# Isolation.net
KiCad netlist of a schematic drawn in Altium Designer
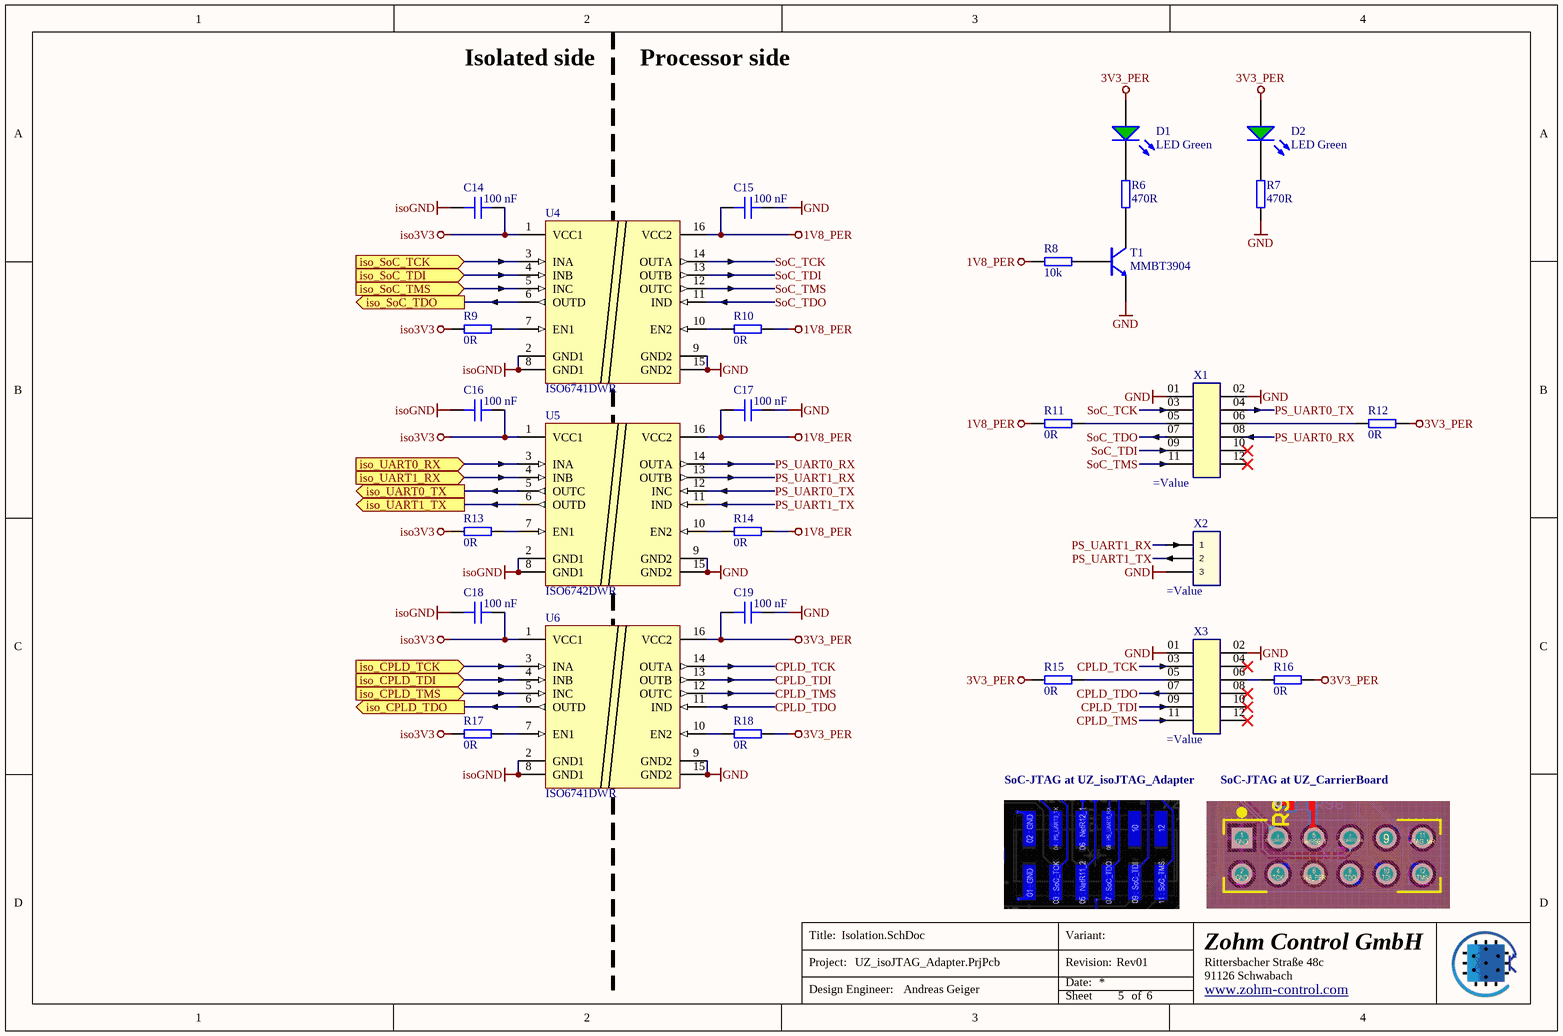
[diagram p0: Isolation.SchDoc]

(export (version "E")
  (design (tool "Eeschema 10.0.6"))
  (components
    (comp (ref "C14")
      (value "100 nF")
      (footprint "C_0402_TE")
      (description "50V 100nF X7R ±10% 0402 Multilayer Ceramic Capacitors MLCC - SMD/SMT ROHS")
      (fields
        (field (name "MANUFACTURER PART NUMBER") "GRM155R71H104KE14D")
        (field (name "MANUFACTURER") "Murata Electronics")
        (field (name "CREATED FROM") "AGeiger")
      )
      (libsource (lib "user") (part "Capacitor"))
    )
    (comp (ref "C15")
      (value "100 nF")
      (footprint "C_0402_TE")
      (description "50V 100nF X7R ±10% 0402 Multilayer Ceramic Capacitors MLCC - SMD/SMT ROHS")
      (fields
        (field (name "MANUFACTURER PART NUMBER") "GRM155R71H104KE14D")
        (field (name "MANUFACTURER") "Murata Electronics")
        (field (name "CREATED FROM") "AGeiger")
      )
      (libsource (lib "user") (part "Capacitor"))
    )
    (comp (ref "C16")
      (value "100 nF")
      (footprint "C_0402_TE")
      (description "50V 100nF X7R ±10% 0402 Multilayer Ceramic Capacitors MLCC - SMD/SMT ROHS")
      (fields
        (field (name "MANUFACTURER PART NUMBER") "GRM155R71H104KE14D")
        (field (name "MANUFACTURER") "Murata Electronics")
        (field (name "CREATED FROM") "AGeiger")
      )
      (libsource (lib "user") (part "Capacitor"))
    )
    (comp (ref "C17")
      (value "100 nF")
      (footprint "C_0402_TE")
      (description "50V 100nF X7R ±10% 0402 Multilayer Ceramic Capacitors MLCC - SMD/SMT ROHS")
      (fields
        (field (name "MANUFACTURER PART NUMBER") "GRM155R71H104KE14D")
        (field (name "MANUFACTURER") "Murata Electronics")
        (field (name "CREATED FROM") "AGeiger")
      )
      (libsource (lib "user") (part "Capacitor"))
    )
    (comp (ref "C18")
      (value "100 nF")
      (footprint "C_0402_TE")
      (description "50V 100nF X7R ±10% 0402 Multilayer Ceramic Capacitors MLCC - SMD/SMT ROHS")
      (fields
        (field (name "MANUFACTURER PART NUMBER") "GRM155R71H104KE14D")
        (field (name "MANUFACTURER") "Murata Electronics")
        (field (name "CREATED FROM") "AGeiger")
      )
      (libsource (lib "user") (part "Capacitor"))
    )
    (comp (ref "C19")
      (value "100 nF")
      (footprint "C_0402_TE")
      (description "50V 100nF X7R ±10% 0402 Multilayer Ceramic Capacitors MLCC - SMD/SMT ROHS")
      (fields
        (field (name "MANUFACTURER PART NUMBER") "GRM155R71H104KE14D")
        (field (name "MANUFACTURER") "Murata Electronics")
        (field (name "CREATED FROM") "AGeiger")
      )
      (libsource (lib "user") (part "Capacitor"))
    )
    (comp (ref "D1")
      (value "LED Green")
      (footprint "WL-SMCW_0603")
      (description "LED GREEN 520~535NM 112~258MCD@20MA TOP VIEW 0603 ROHS")
      (fields
        (field (name "MANUFACTURER PART NUMBER") "19-217/GHC-YR1S2/3T")
        (field (name "MANUFACTURER") "Everlight Elec")
        (field (name "CREATED FROM") "T. Wendt")
      )
      (libsource (lib "user") (part "LED_Green"))
    )
    (comp (ref "D2")
      (value "LED Green")
      (footprint "WL-SMCW_0603")
      (description "LED GREEN 520~535NM 112~258MCD@20MA TOP VIEW 0603 ROHS")
      (fields
        (field (name "MANUFACTURER PART NUMBER") "19-217/GHC-YR1S2/3T")
        (field (name "MANUFACTURER") "Everlight Elec")
        (field (name "CREATED FROM") "T. Wendt")
      )
      (libsource (lib "user") (part "LED_Green"))
    )
    (comp (ref "R6")
      (value "470R")
      (footprint "RES 0603_1608")
      (description "SMD resistor E24 series")
      (fields
        (field (name "MANUFACTURER PART NUMBER") "RK73B1JTTD471J")
        (field (name "MANUFACTURER") "KOA Speer")
        (field (name "CREATED FROM") "MGremer")
      )
      (libsource (lib "user") (part "Resistor"))
    )
    (comp (ref "R7")
      (value "470R")
      (footprint "RES 0603_1608")
      (description "SMD resistor E24 series")
      (fields
        (field (name "MANUFACTURER PART NUMBER") "RK73B1JTTD471J")
        (field (name "MANUFACTURER") "KOA Speer")
        (field (name "CREATED FROM") "MGremer")
      )
      (libsource (lib "user") (part "Resistor"))
    )
    (comp (ref "R8")
      (value "10k")
      (footprint "RES 0603_1608")
      (description "SMD resistor 1%")
      (fields
        (field (name "MANUFACTURER PART NUMBER") "0603WAF1002T5E")
        (field (name "MANUFACTURER") "UNI-ROYAL")
        (field (name "CREATED FROM") "AGeiger")
      )
      (libsource (lib "user") (part "Resistor"))
    )
    (comp (ref "R9")
      (value "0R")
      (footprint "R_0402_TE")
      (description "62.5mW Thick Film Resistors 50V 0Ω 0402 Chip Resistor - Surface Mount ROHS")
      (fields
        (field (name "MANUFACTURER PART NUMBER") "RC0402JR-070RL")
        (field (name "MANUFACTURER") "YAGEO")
        (field (name "CREATED FROM") "AGeiger")
      )
      (libsource (lib "user") (part "Resistor"))
    )
    (comp (ref "R10")
      (value "0R")
      (footprint "R_0402_TE")
      (description "62.5mW Thick Film Resistors 50V 0Ω 0402 Chip Resistor - Surface Mount ROHS")
      (fields
        (field (name "MANUFACTURER PART NUMBER") "RC0402JR-070RL")
        (field (name "MANUFACTURER") "YAGEO")
        (field (name "CREATED FROM") "AGeiger")
      )
      (libsource (lib "user") (part "Resistor"))
    )
    (comp (ref "R11")
      (value "0R")
      (footprint "R_0402_TE")
      (description "62.5mW Thick Film Resistors 50V 0Ω 0402 Chip Resistor - Surface Mount ROHS")
      (fields
        (field (name "MANUFACTURER PART NUMBER") "RC0402JR-070RL")
        (field (name "MANUFACTURER") "YAGEO")
        (field (name "CREATED FROM") "AGeiger")
      )
      (libsource (lib "user") (part "Resistor"))
    )
    (comp (ref "R12")
      (value "0R")
      (footprint "R_0402_TE")
      (description "62.5mW Thick Film Resistors 50V 0Ω 0402 Chip Resistor - Surface Mount ROHS")
      (fields
        (field (name "MANUFACTURER PART NUMBER") "RC0402JR-070RL")
        (field (name "MANUFACTURER") "YAGEO")
        (field (name "CREATED FROM") "AGeiger")
      )
      (libsource (lib "user") (part "Resistor"))
    )
    (comp (ref "R13")
      (value "0R")
      (footprint "R_0402_TE")
      (description "62.5mW Thick Film Resistors 50V 0Ω 0402 Chip Resistor - Surface Mount ROHS")
      (fields
        (field (name "MANUFACTURER PART NUMBER") "RC0402JR-070RL")
        (field (name "MANUFACTURER") "YAGEO")
        (field (name "CREATED FROM") "AGeiger")
      )
      (libsource (lib "user") (part "Resistor"))
    )
    (comp (ref "R14")
      (value "0R")
      (footprint "R_0402_TE")
      (description "62.5mW Thick Film Resistors 50V 0Ω 0402 Chip Resistor - Surface Mount ROHS")
      (fields
        (field (name "MANUFACTURER PART NUMBER") "RC0402JR-070RL")
        (field (name "MANUFACTURER") "YAGEO")
        (field (name "CREATED FROM") "AGeiger")
      )
      (libsource (lib "user") (part "Resistor"))
    )
    (comp (ref "R15")
      (value "0R")
      (footprint "R_0402_TE")
      (description "62.5mW Thick Film Resistors 50V 0Ω 0402 Chip Resistor - Surface Mount ROHS")
      (fields
        (field (name "MANUFACTURER PART NUMBER") "RC0402JR-070RL")
        (field (name "MANUFACTURER") "YAGEO")
        (field (name "CREATED FROM") "AGeiger")
      )
      (libsource (lib "user") (part "Resistor"))
    )
    (comp (ref "R16")
      (value "0R")
      (footprint "R_0402_TE")
      (description "62.5mW Thick Film Resistors 50V 0Ω 0402 Chip Resistor - Surface Mount ROHS")
      (fields
        (field (name "MANUFACTURER PART NUMBER") "RC0402JR-070RL")
        (field (name "MANUFACTURER") "YAGEO")
        (field (name "CREATED FROM") "AGeiger")
      )
      (libsource (lib "user") (part "Resistor"))
    )
    (comp (ref "R17")
      (value "0R")
      (footprint "R_0402_TE")
      (description "62.5mW Thick Film Resistors 50V 0Ω 0402 Chip Resistor - Surface Mount ROHS")
      (fields
        (field (name "MANUFACTURER PART NUMBER") "RC0402JR-070RL")
        (field (name "MANUFACTURER") "YAGEO")
        (field (name "CREATED FROM") "AGeiger")
      )
      (libsource (lib "user") (part "Resistor"))
    )
    (comp (ref "R18")
      (value "0R")
      (footprint "R_0402_TE")
      (description "62.5mW Thick Film Resistors 50V 0Ω 0402 Chip Resistor - Surface Mount ROHS")
      (fields
        (field (name "MANUFACTURER PART NUMBER") "RC0402JR-070RL")
        (field (name "MANUFACTURER") "YAGEO")
        (field (name "CREATED FROM") "AGeiger")
      )
      (libsource (lib "user") (part "Resistor"))
    )
    (comp (ref "T1")
      (value "MMBT3904")
      (footprint "SOT-23-3")
      (description "40V 200mW 100@10mA,1V 200mA NPN SOT-23 Bipolar Transistors - BJT ROHS")
      (fields
        (field (name "MANUFACTURER") "Jiangsu Changjing Electronics Technology")
        (field (name "LCSC PART NUMBER") "C20526")
        (field (name "CREATED FROM") "AGeiger")
      )
      (libsource (lib "user") (part "NPN-SOT23"))
    )
    (comp (ref "U4")
      (value "ISO6741DWR")
      (footprint "SOIC127P1030X265-16N")
      (description "Digital Isolators General-purpose, quad-channel, 3/1 digital isolator 16-SOIC -40 to 125")
      (fields
        (field (name "MANUFACTURER") "Texas Instruments")
        (field (name "LCSC PART NUMBER") "C5216432")
        (field (name "CREATED FROM") "AGeiger")
      )
      (libsource (lib "user") (part "ISO6741"))
    )
    (comp (ref "U5")
      (value "ISO6742DWR")
      (footprint "SOIC127P1030X265-16N")
      (description "Digital Isolators General-purpose, quad-channel, 2/2 digital isolator")
      (fields
        (field (name "MANUFACTURER") "Texas Instruments")
        (field (name "LCSC PART NUMBER") "C9900001820")
        (field (name "CREATED FROM") "AGeiger")
      )
      (libsource (lib "user") (part "ISO6742"))
    )
    (comp (ref "U6")
      (value "ISO6741DWR")
      (footprint "SOIC127P1030X265-16N")
      (description "Digital Isolators General-purpose, quad-channel, 3/1 digital isolator 16-SOIC -40 to 125")
      (fields
        (field (name "MANUFACTURER") "Texas Instruments")
        (field (name "LCSC PART NUMBER") "C5216432")
        (field (name "CREATED FROM") "AGeiger")
      )
      (libsource (lib "user") (part "ISO6741"))
    )
    (comp (ref "X1")
      (value "~")
      (footprint "SSW-106-22-F-D-VS")
      (description "Tiger Buy™ Socket Strip with PCB Tails, .100\" Pitch")
      (fields
        (field (name "MANUFACTURER PART NUMBER") "SSW-106-22-F-D-VS")
        (field (name "MANUFACTURER") "SAMTEC")
        (field (name "CREATED FROM") "AGeiger")
      )
      (libsource (lib "user") (part "SSW-106-22-F-D-VS"))
    )
    (comp (ref "X2")
      (value "~")
      (footprint "TSW-103-XX-XXX-S")
      (description "Classic PCB Header Strips, 0.100\" pitch")
      (fields
        (field (name "MANUFACTURER") "SAMTEC")
        (field (name "MANUFACTURER PART NUMBER") "TSW-103-07-L-S")
        (field (name "CREATED") "2020_11_26_AGeiger")
        (field (name "CREATED FROM") "AGeiger")
      )
      (libsource (lib "user") (part "TSW-103-XX-XXX-S"))
    )
    (comp (ref "X3")
      (value "~")
      (footprint "TSM-106-01-L-DV")
      (description ".100\" Surface Mount Terminal Strip")
      (fields
        (field (name "MANUFACTURER PART NUMBER") "TSM-106-01-L-DV")
        (field (name "MANUFACTURER") "SAMTEC")
        (field (name "CREATED FROM") "AGeiger")
      )
      (libsource (lib "user") (part "TSM-106-01-L-DV"))
    )
  )
  (nets
    (net (code "1") (name "/CPLD_TCK") (class "Default")
      (node (ref "U6") (pin "14") (pinfunction "OUTA_14") (pintype "output"))
      (node (ref "X3") (pin "03") (pinfunction "03_03") (pintype "passive"))
    )
    (net (code "2") (name "/CPLD_TDI") (class "Default")
      (node (ref "U6") (pin "13") (pinfunction "OUTB_13") (pintype "output"))
      (node (ref "X3") (pin "09") (pinfunction "09_09") (pintype "passive"))
    )
    (net (code "3") (name "/CPLD_TDO") (class "Default")
      (node (ref "U6") (pin "11") (pinfunction "IND_11") (pintype "input"))
      (node (ref "X3") (pin "07") (pinfunction "07_07") (pintype "passive"))
    )
    (net (code "4") (name "/CPLD_TMS") (class "Default")
      (node (ref "U6") (pin "12") (pinfunction "OUTC_12") (pintype "output"))
      (node (ref "X3") (pin "11") (pinfunction "11_11") (pintype "passive"))
    )
    (net (code "5") (name "/PS_UART0_RX") (class "Default")
      (node (ref "U5") (pin "14") (pinfunction "OUTA_14") (pintype "output"))
      (node (ref "X1") (pin "08") (pinfunction "08_08") (pintype "passive"))
    )
    (net (code "6") (name "/PS_UART0_TX") (class "Default")
      (node (ref "U5") (pin "12") (pinfunction "INC_12") (pintype "input"))
      (node (ref "X1") (pin "04") (pinfunction "04_04") (pintype "passive"))
    )
    (net (code "7") (name "/PS_UART1_RX") (class "Default")
      (node (ref "U5") (pin "13") (pinfunction "OUTB_13") (pintype "output"))
      (node (ref "X2") (pin "1") (pinfunction "1_1") (pintype "passive"))
    )
    (net (code "8") (name "/PS_UART1_TX") (class "Default")
      (node (ref "U5") (pin "11") (pinfunction "IND_11") (pintype "input"))
      (node (ref "X2") (pin "2") (pinfunction "2_2") (pintype "passive"))
    )
    (net (code "9") (name "/SoC_TCK") (class "Default")
      (node (ref "U4") (pin "14") (pinfunction "OUTA_14") (pintype "output"))
      (node (ref "X1") (pin "03") (pinfunction "03_03") (pintype "passive"))
    )
    (net (code "10") (name "/SoC_TDI") (class "Default")
      (node (ref "U4") (pin "13") (pinfunction "OUTB_13") (pintype "output"))
      (node (ref "X1") (pin "09") (pinfunction "09_09") (pintype "passive"))
    )
    (net (code "11") (name "/SoC_TDO") (class "Default")
      (node (ref "U4") (pin "11") (pinfunction "IND_11") (pintype "input"))
      (node (ref "X1") (pin "07") (pinfunction "07_07") (pintype "passive"))
    )
    (net (code "12") (name "/SoC_TMS") (class "Default")
      (node (ref "U4") (pin "12") (pinfunction "OUTC_12") (pintype "output"))
      (node (ref "X1") (pin "11") (pinfunction "11_11") (pintype "passive"))
    )
    (net (code "13") (name "/iso_CPLD_TCK") (class "Default")
      (node (ref "U6") (pin "3") (pinfunction "INA_3") (pintype "input"))
    )
    (net (code "14") (name "/iso_CPLD_TDI") (class "Default")
      (node (ref "U6") (pin "4") (pinfunction "INB_4") (pintype "input"))
    )
    (net (code "15") (name "/iso_CPLD_TDO") (class "Default")
      (node (ref "U6") (pin "6") (pinfunction "OUTD_6") (pintype "output"))
    )
    (net (code "16") (name "/iso_CPLD_TMS") (class "Default")
      (node (ref "U6") (pin "5") (pinfunction "INC_5") (pintype "input"))
    )
    (net (code "17") (name "/iso_SoC_TCK") (class "Default")
      (node (ref "U4") (pin "3") (pinfunction "INA_3") (pintype "input"))
    )
    (net (code "18") (name "/iso_SoC_TDI") (class "Default")
      (node (ref "U4") (pin "4") (pinfunction "INB_4") (pintype "input"))
    )
    (net (code "19") (name "/iso_SoC_TDO") (class "Default")
      (node (ref "U4") (pin "6") (pinfunction "OUTD_6") (pintype "output"))
    )
    (net (code "20") (name "/iso_SoC_TMS") (class "Default")
      (node (ref "U4") (pin "5") (pinfunction "INC_5") (pintype "input"))
    )
    (net (code "21") (name "/iso_UART0_RX") (class "Default")
      (node (ref "U5") (pin "3") (pinfunction "INA_3") (pintype "input"))
    )
    (net (code "22") (name "/iso_UART0_TX") (class "Default")
      (node (ref "U5") (pin "5") (pinfunction "OUTC_5") (pintype "output"))
    )
    (net (code "23") (name "/iso_UART1_RX") (class "Default")
      (node (ref "U5") (pin "4") (pinfunction "INB_4") (pintype "input"))
    )
    (net (code "24") (name "/iso_UART1_TX") (class "Default")
      (node (ref "U5") (pin "6") (pinfunction "OUTD_6") (pintype "output"))
    )
    (net (code "25") (name "1V8_PER") (class "Default")
      (node (ref "C15") (pin "2") (pinfunction "2_2") (pintype "passive"))
      (node (ref "C17") (pin "2") (pinfunction "2_2") (pintype "passive"))
      (node (ref "R10") (pin "2") (pinfunction "2_2") (pintype "passive"))
      (node (ref "R11") (pin "1") (pinfunction "1_1") (pintype "passive"))
      (node (ref "R14") (pin "2") (pinfunction "2_2") (pintype "passive"))
      (node (ref "R8") (pin "2") (pinfunction "2_2") (pintype "passive"))
      (node (ref "U4") (pin "16") (pinfunction "VCC2_16") (pintype "power_in"))
      (node (ref "U5") (pin "16") (pinfunction "VCC2_16") (pintype "power_in"))
    )
    (net (code "26") (name "3V3_PER") (class "Default")
      (node (ref "C19") (pin "2") (pinfunction "2_2") (pintype "passive"))
      (node (ref "D1") (pin "2") (pinfunction "A_2") (pintype "passive"))
      (node (ref "D2") (pin "2") (pinfunction "A_2") (pintype "passive"))
      (node (ref "R12") (pin "2") (pinfunction "2_2") (pintype "passive"))
      (node (ref "R15") (pin "1") (pinfunction "1_1") (pintype "passive"))
      (node (ref "R16") (pin "2") (pinfunction "2_2") (pintype "passive"))
      (node (ref "R18") (pin "2") (pinfunction "2_2") (pintype "passive"))
      (node (ref "U6") (pin "16") (pinfunction "VCC2_16") (pintype "power_in"))
    )
    (net (code "27") (name "GND") (class "Default")
      (node (ref "C15") (pin "1") (pinfunction "1_1") (pintype "passive"))
      (node (ref "C17") (pin "1") (pinfunction "1_1") (pintype "passive"))
      (node (ref "C19") (pin "1") (pinfunction "1_1") (pintype "passive"))
      (node (ref "R7") (pin "1") (pinfunction "1_1") (pintype "passive"))
      (node (ref "T1") (pin "2") (pinfunction "EMITTER_2") (pintype "passive"))
      (node (ref "U4") (pin "15") (pinfunction "GND2_15") (pintype "power_in"))
      (node (ref "U4") (pin "9") (pinfunction "GND2_9") (pintype "power_in"))
      (node (ref "U5") (pin "15") (pinfunction "GND2_15") (pintype "power_in"))
      (node (ref "U5") (pin "9") (pinfunction "GND2_9") (pintype "power_in"))
      (node (ref "U6") (pin "15") (pinfunction "GND2_15") (pintype "power_in"))
      (node (ref "U6") (pin "9") (pinfunction "GND2_9") (pintype "power_in"))
      (node (ref "X1") (pin "01") (pinfunction "01_01") (pintype "passive"))
      (node (ref "X1") (pin "02") (pinfunction "02_02") (pintype "passive"))
      (node (ref "X2") (pin "3") (pinfunction "3_3") (pintype "passive"))
      (node (ref "X3") (pin "01") (pinfunction "01_01") (pintype "passive"))
      (node (ref "X3") (pin "02") (pinfunction "02_02") (pintype "passive"))
    )
    (net (code "28") (name "Net-(D1-K)") (class "Default")
      (node (ref "D1") (pin "1") (pinfunction "K_1") (pintype "passive"))
      (node (ref "R6") (pin "2") (pinfunction "2_2") (pintype "passive"))
    )
    (net (code "29") (name "Net-(D2-K)") (class "Default")
      (node (ref "D2") (pin "1") (pinfunction "K_1") (pintype "passive"))
      (node (ref "R7") (pin "2") (pinfunction "2_2") (pintype "passive"))
    )
    (net (code "30") (name "Net-(R11-Pad2)") (class "Default")
      (node (ref "R11") (pin "2") (pinfunction "2_2") (pintype "passive"))
      (node (ref "X1") (pin "05") (pinfunction "05_05") (pintype "passive"))
    )
    (net (code "31") (name "Net-(R12-Pad1)") (class "Default")
      (node (ref "R12") (pin "1") (pinfunction "1_1") (pintype "passive"))
      (node (ref "X1") (pin "06") (pinfunction "06_06") (pintype "passive"))
    )
    (net (code "32") (name "Net-(R15-Pad2)") (class "Default")
      (node (ref "R15") (pin "2") (pinfunction "2_2") (pintype "passive"))
      (node (ref "X3") (pin "05") (pinfunction "05_05") (pintype "passive"))
    )
    (net (code "33") (name "Net-(R16-Pad1)") (class "Default")
      (node (ref "R16") (pin "1") (pinfunction "1_1") (pintype "passive"))
      (node (ref "X3") (pin "06") (pinfunction "06_06") (pintype "passive"))
    )
    (net (code "34") (name "Net-(T1-BASIS)") (class "Default")
      (node (ref "R8") (pin "1") (pinfunction "1_1") (pintype "passive"))
      (node (ref "T1") (pin "1") (pinfunction "BASIS_1") (pintype "passive"))
    )
    (net (code "35") (name "Net-(T1-COLLECTOR)") (class "Default")
      (node (ref "R6") (pin "1") (pinfunction "1_1") (pintype "passive"))
      (node (ref "T1") (pin "3") (pinfunction "COLLECTOR_3") (pintype "passive"))
    )
    (net (code "36") (name "Net-(U4-EN1)") (class "Default")
      (node (ref "R9") (pin "2") (pinfunction "2_2") (pintype "passive"))
      (node (ref "U4") (pin "7") (pinfunction "EN1_7") (pintype "input"))
    )
    (net (code "37") (name "Net-(U4-EN2)") (class "Default")
      (node (ref "R10") (pin "1") (pinfunction "1_1") (pintype "passive"))
      (node (ref "U4") (pin "10") (pinfunction "EN2_10") (pintype "input"))
    )
    (net (code "38") (name "Net-(U5-EN1)") (class "Default")
      (node (ref "R13") (pin "2") (pinfunction "2_2") (pintype "passive"))
      (node (ref "U5") (pin "7") (pinfunction "EN1_7") (pintype "input"))
    )
    (net (code "39") (name "Net-(U5-EN2)") (class "Default")
      (node (ref "R14") (pin "1") (pinfunction "1_1") (pintype "passive"))
      (node (ref "U5") (pin "10") (pinfunction "EN2_10") (pintype "input"))
    )
    (net (code "40") (name "Net-(U6-EN1)") (class "Default")
      (node (ref "R17") (pin "2") (pinfunction "2_2") (pintype "passive"))
      (node (ref "U6") (pin "7") (pinfunction "EN1_7") (pintype "input"))
    )
    (net (code "41") (name "Net-(U6-EN2)") (class "Default")
      (node (ref "R18") (pin "1") (pinfunction "1_1") (pintype "passive"))
      (node (ref "U6") (pin "10") (pinfunction "EN2_10") (pintype "input"))
    )
    (net (code "42") (name "iso3V3") (class "Default")
      (node (ref "C14") (pin "1") (pinfunction "1_1") (pintype "passive"))
      (node (ref "C16") (pin "1") (pinfunction "1_1") (pintype "passive"))
      (node (ref "C18") (pin "1") (pinfunction "1_1") (pintype "passive"))
      (node (ref "R13") (pin "1") (pinfunction "1_1") (pintype "passive"))
      (node (ref "R17") (pin "1") (pinfunction "1_1") (pintype "passive"))
      (node (ref "R9") (pin "1") (pinfunction "1_1") (pintype "passive"))
      (node (ref "U4") (pin "1") (pinfunction "VCC1_1") (pintype "power_in"))
      (node (ref "U5") (pin "1") (pinfunction "VCC1_1") (pintype "power_in"))
      (node (ref "U6") (pin "1") (pinfunction "VCC1_1") (pintype "power_in"))
    )
    (net (code "43") (name "isoGND") (class "Default")
      (node (ref "C14") (pin "2") (pinfunction "2_2") (pintype "passive"))
      (node (ref "C16") (pin "2") (pinfunction "2_2") (pintype "passive"))
      (node (ref "C18") (pin "2") (pinfunction "2_2") (pintype "passive"))
      (node (ref "U4") (pin "2") (pinfunction "GND1_2") (pintype "power_in"))
      (node (ref "U4") (pin "8") (pinfunction "GND1_8") (pintype "power_in"))
      (node (ref "U5") (pin "2") (pinfunction "GND1_2") (pintype "power_in"))
      (node (ref "U5") (pin "8") (pinfunction "GND1_8") (pintype "power_in"))
      (node (ref "U6") (pin "2") (pinfunction "GND1_2") (pintype "power_in"))
      (node (ref "U6") (pin "8") (pinfunction "GND1_8") (pintype "power_in"))
    )
    (net (code "44") (name "unconnected-(X1-Pad10)") (class "Default")
      (node (ref "X1") (pin "10") (pinfunction "10_10") (pintype "passive+no_connect"))
    )
    (net (code "45") (name "unconnected-(X1-Pad12)") (class "Default")
      (node (ref "X1") (pin "12") (pinfunction "12_12") (pintype "passive+no_connect"))
    )
    (net (code "46") (name "unconnected-(X3-Pad04)") (class "Default")
      (node (ref "X3") (pin "04") (pinfunction "04_04") (pintype "passive+no_connect"))
    )
    (net (code "47") (name "unconnected-(X3-Pad08)") (class "Default")
      (node (ref "X3") (pin "08") (pinfunction "08_08") (pintype "passive+no_connect"))
    )
    (net (code "48") (name "unconnected-(X3-Pad10)") (class "Default")
      (node (ref "X3") (pin "10") (pinfunction "10_10") (pintype "passive+no_connect"))
    )
    (net (code "49") (name "unconnected-(X3-Pad12)") (class "Default")
      (node (ref "X3") (pin "12") (pinfunction "12_12") (pintype "passive+no_connect"))
    )
  )
)
